# MAGI_sBoostPower.net
KiCad netlist of a schematic drawn in Altium Designer
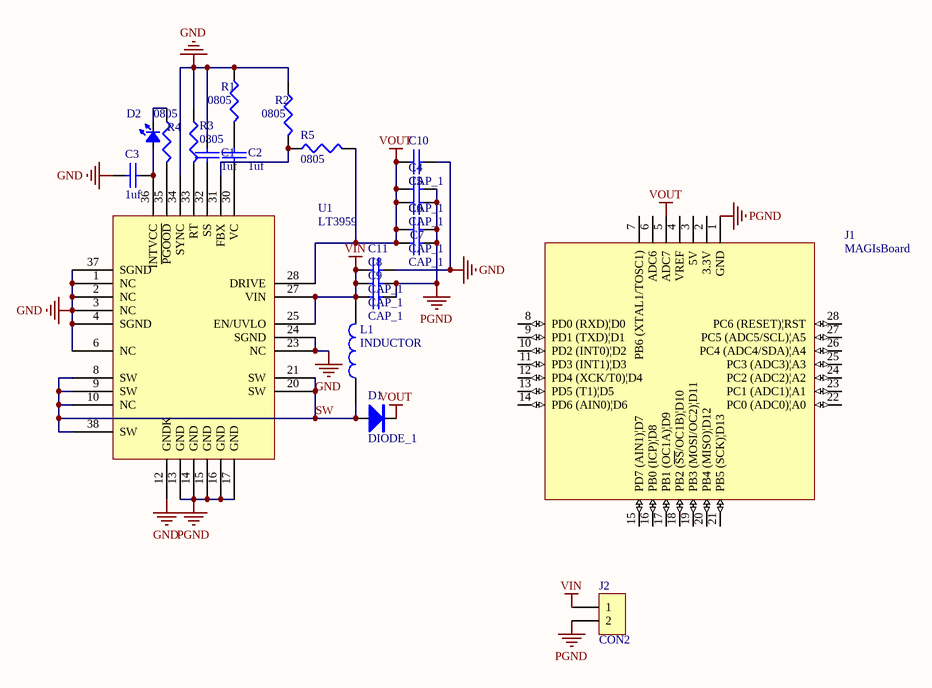
[diagram p0: MAGI'sBoostPower.SchDoc]

(export (version "E")
  (design (tool "Eeschema 10.0.6"))
  (components
    (comp (ref "C1")
      (value "1uf")
      (footprint "6-0805_N")
      (description "Capacitor")
      (libsource (lib "电容器") (part "CAP_1"))
    )
    (comp (ref "C2")
      (value "1uf")
      (footprint "6-0805_N")
      (description "Capacitor")
      (libsource (lib "电容器") (part "CAP_1"))
    )
    (comp (ref "C3")
      (value "1uf")
      (footprint "6-0805_N")
      (description "Capacitor")
      (libsource (lib "电容器") (part "CAP_1"))
    )
    (comp (ref "C4")
      (value "CAP_1")
      (footprint "C1206")
      (description "Capacitor")
      (libsource (lib "电容器") (part "CAP_1"))
    )
    (comp (ref "C5")
      (value "CAP_1")
      (footprint "C1206")
      (description "Capacitor")
      (libsource (lib "电容器") (part "CAP_1"))
    )
    (comp (ref "C6")
      (value "CAP_1")
      (footprint "C1206")
      (description "Capacitor")
      (libsource (lib "电容器") (part "CAP_1"))
    )
    (comp (ref "C7")
      (value "CAP_1")
      (footprint "C1206")
      (description "Capacitor")
      (libsource (lib "电容器") (part "CAP_1"))
    )
    (comp (ref "C8")
      (value "CAP_1")
      (footprint "C1206")
      (description "Capacitor")
      (libsource (lib "电容器") (part "CAP_1"))
    )
    (comp (ref "C9")
      (value "CAP_1")
      (footprint "C1206")
      (description "Capacitor")
      (libsource (lib "电容器") (part "CAP_1"))
    )
    (comp (ref "C10")
      (value "CAP_1")
      (footprint "6-0805_n")
      (description "Capacitor")
      (libsource (lib "电容器") (part "CAP_1"))
    )
    (comp (ref "C11")
      (value "CAP_1")
      (footprint "6-0805_n")
      (description "Capacitor")
      (libsource (lib "电容器") (part "CAP_1"))
    )
    (comp (ref "D1")
      (value "DIODE_1")
      (footprint "SMC")
      (description "Diode")
      (libsource (lib "二极管") (part "DIODE_1"))
    )
    (comp (ref "D2")
      (value "LED_0805")
      (footprint "6-0805_n")
      (description "LED")
      (libsource (lib "SCH_Active") (part "LED_0805"))
    )
    (comp (ref "J1")
      (value "MAGIsBoard")
      (footprint "MAGIsBoard")
      (libsource (lib "MAGIsBoard") (part "MAGIsBoard"))
    )
    (comp (ref "J2")
      (value "CON2")
      (footprint "T-Mini")
      (description "Connector")
      (libsource (lib "CON系列") (part "CON2"))
    )
    (comp (ref "L1") (value "INDUCTOR") (footprint "10*10") (libsource (lib "汇总") (part "INDUCTOR")))
    (comp (ref "R1") (value "0805") (footprint "6-0805_N") (libsource (lib "电阻器") (part "RES1_1")))
    (comp (ref "R2") (value "0805") (footprint "6-0805_N") (libsource (lib "电阻器") (part "RES1_1")))
    (comp (ref "R3") (value "0805") (footprint "6-0805_N") (libsource (lib "电阻器") (part "RES1_1")))
    (comp (ref "R4") (value "0805") (footprint "6-0805_N") (libsource (lib "电阻器") (part "RES1_1")))
    (comp (ref "R5") (value "0805") (footprint "6-0805_N") (libsource (lib "电阻器") (part "RES1_1")))
    (comp (ref "U1") (value "LT3959") (footprint "LT3959") (libsource (lib "PMIC") (part "LT3959")))
  )
  (nets
    (net (code "1") (name "/SW") (class "Default")
      (node (ref "D1") (pin "1") (pinfunction "A_1") (pintype "passive"))
      (node (ref "L1") (pin "1") (pinfunction "1_1") (pintype "passive"))
      (node (ref "U1") (pin "10") (pinfunction "NC_10") (pintype "passive"))
      (node (ref "U1") (pin "20") (pinfunction "SW_20") (pintype "passive"))
      (node (ref "U1") (pin "21") (pinfunction "SW_21") (pintype "passive"))
      (node (ref "U1") (pin "38") (pinfunction "SW_38") (pintype "passive"))
      (node (ref "U1") (pin "8") (pinfunction "SW_8") (pintype "passive"))
      (node (ref "U1") (pin "9") (pinfunction "SW_9") (pintype "passive"))
    )
    (net (code "2") (name "GND") (class "Default")
      (node (ref "C1") (pin "2") (pinfunction "2_2") (pintype "passive"))
      (node (ref "C10") (pin "2") (pinfunction "2_2") (pintype "passive"))
      (node (ref "C11") (pin "2") (pinfunction "2_2") (pintype "passive"))
      (node (ref "C3") (pin "2") (pinfunction "2_2") (pintype "passive"))
      (node (ref "R1") (pin "1") (pinfunction "1_1") (pintype "passive"))
      (node (ref "R2") (pin "1") (pinfunction "1_1") (pintype "passive"))
      (node (ref "R3") (pin "1") (pinfunction "1_1") (pintype "passive"))
      (node (ref "U1") (pin "1") (pinfunction "NC_1") (pintype "passive"))
      (node (ref "U1") (pin "12") (pinfunction "GNDK_12") (pintype "passive"))
      (node (ref "U1") (pin "2") (pinfunction "NC_2") (pintype "passive"))
      (node (ref "U1") (pin "23") (pinfunction "NC_23") (pintype "passive"))
      (node (ref "U1") (pin "24") (pinfunction "SGND_24") (pintype "passive"))
      (node (ref "U1") (pin "3") (pinfunction "NC_3") (pintype "passive"))
      (node (ref "U1") (pin "34") (pinfunction "SYNC_34") (pintype "passive"))
      (node (ref "U1") (pin "37") (pinfunction "SGND_37") (pintype "passive"))
      (node (ref "U1") (pin "4") (pinfunction "SGND_4") (pintype "passive"))
      (node (ref "U1") (pin "6") (pinfunction "NC_6") (pintype "passive"))
    )
    (net (code "3") (name "Net-(C2-Pad2)") (class "Default")
      (node (ref "C2") (pin "2") (pinfunction "2_2") (pintype "passive"))
      (node (ref "R1") (pin "2") (pinfunction "2_2") (pintype "passive"))
    )
    (net (code "4") (name "Net-(D2-A)") (class "Default")
      (node (ref "C3") (pin "1") (pinfunction "1_1") (pintype "passive"))
      (node (ref "D2") (pin "1") (pinfunction "A_1") (pintype "passive"))
      (node (ref "U1") (pin "36") (pinfunction "INTVCC_36") (pintype "passive"))
    )
    (net (code "5") (name "Net-(D2-K)") (class "Default")
      (node (ref "D2") (pin "2") (pinfunction "K_2") (pintype "passive"))
      (node (ref "R4") (pin "1") (pinfunction "1_1") (pintype "passive"))
    )
    (net (code "6") (name "Net-(U1-FBX)") (class "Default")
      (node (ref "R2") (pin "2") (pinfunction "2_2") (pintype "passive"))
      (node (ref "R5") (pin "1") (pinfunction "1_1") (pintype "passive"))
      (node (ref "U1") (pin "31") (pinfunction "FBX_31") (pintype "passive"))
    )
    (net (code "7") (name "Net-(U1-RT)") (class "Default")
      (node (ref "R3") (pin "2") (pinfunction "2_2") (pintype "passive"))
      (node (ref "U1") (pin "33") (pinfunction "RT_33") (pintype "passive"))
    )
    (net (code "8") (name "Net-(U1-SS)") (class "Default")
      (node (ref "C1") (pin "1") (pinfunction "1_1") (pintype "passive"))
      (node (ref "U1") (pin "32") (pinfunction "SS_32") (pintype "passive"))
    )
    (net (code "9") (name "Net-(U1-VC)") (class "Default")
      (node (ref "C2") (pin "1") (pinfunction "1_1") (pintype "passive"))
      (node (ref "U1") (pin "30") (pinfunction "VC_30") (pintype "passive"))
    )
    (net (code "10") (name "Net-(U1-~{PGOOD})") (class "Default")
      (node (ref "R4") (pin "2") (pinfunction "2_2") (pintype "passive"))
      (node (ref "U1") (pin "35") (pinfunction "~{PGOOD}_35") (pintype "passive"))
    )
    (net (code "11") (name "PGND") (class "Default")
      (node (ref "C4") (pin "2") (pinfunction "2_2") (pintype "passive"))
      (node (ref "C5") (pin "2") (pinfunction "2_2") (pintype "passive"))
      (node (ref "C6") (pin "2") (pinfunction "2_2") (pintype "passive"))
      (node (ref "C7") (pin "2") (pinfunction "2_2") (pintype "passive"))
      (node (ref "C8") (pin "2") (pinfunction "2_2") (pintype "passive"))
      (node (ref "C9") (pin "2") (pinfunction "2_2") (pintype "passive"))
      (node (ref "J1") (pin "1") (pinfunction "GND_1") (pintype "power_in"))
      (node (ref "J2") (pin "2") (pinfunction "2_2") (pintype "passive"))
      (node (ref "U1") (pin "13") (pinfunction "GND_13") (pintype "passive"))
      (node (ref "U1") (pin "14") (pinfunction "GND_14") (pintype "passive"))
      (node (ref "U1") (pin "15") (pinfunction "GND_15") (pintype "passive"))
      (node (ref "U1") (pin "16") (pinfunction "GND_16") (pintype "passive"))
      (node (ref "U1") (pin "17") (pinfunction "GND_17") (pintype "passive"))
    )
    (net (code "12") (name "VIN") (class "Default")
      (node (ref "C11") (pin "1") (pinfunction "1_1") (pintype "passive"))
      (node (ref "C8") (pin "1") (pinfunction "1_1") (pintype "passive"))
      (node (ref "C9") (pin "1") (pinfunction "1_1") (pintype "passive"))
      (node (ref "J2") (pin "1") (pinfunction "1_1") (pintype "passive"))
      (node (ref "L1") (pin "2") (pinfunction "2_2") (pintype "passive"))
      (node (ref "U1") (pin "25") (pinfunction "EN/UVLO_25") (pintype "passive"))
      (node (ref "U1") (pin "27") (pinfunction "VIN_27") (pintype "passive"))
    )
    (net (code "13") (name "VOUT") (class "Default")
      (node (ref "C10") (pin "1") (pinfunction "1_1") (pintype "passive"))
      (node (ref "C4") (pin "1") (pinfunction "1_1") (pintype "passive"))
      (node (ref "C5") (pin "1") (pinfunction "1_1") (pintype "passive"))
      (node (ref "C6") (pin "1") (pinfunction "1_1") (pintype "passive"))
      (node (ref "C7") (pin "1") (pinfunction "1_1") (pintype "passive"))
      (node (ref "D1") (pin "2") (pinfunction "K_2") (pintype "passive"))
      (node (ref "J1") (pin "5") (pinfunction "ADC7_5") (pintype "passive"))
      (node (ref "R5") (pin "2") (pinfunction "2_2") (pintype "passive"))
      (node (ref "U1") (pin "28") (pinfunction "DRIVE_28") (pintype "passive"))
    )
    (net (code "14") (name "unconnected-(J1-3.3V-Pad2)") (class "Default")
      (node (ref "J1") (pin "2") (pinfunction "3.3V_2") (pintype "power_in"))
    )
    (net (code "15") (name "unconnected-(J1-5V-Pad3)") (class "Default")
      (node (ref "J1") (pin "3") (pinfunction "5V_3") (pintype "power_in"))
    )
    (net (code "16") (name "unconnected-(J1-ADC6-Pad6)") (class "Default")
      (node (ref "J1") (pin "6") (pinfunction "ADC6_6") (pintype "passive"))
    )
    (net (code "17") (name "unconnected-(J1-PB0_(ICP)¦D8-Pad16)") (class "Default")
      (node (ref "J1") (pin "16") (pinfunction "PB0_(ICP)¦D8_16") (pintype "bidirectional"))
    )
    (net (code "18") (name "unconnected-(J1-PB1_(OC1A)¦D9-Pad17)") (class "Default")
      (node (ref "J1") (pin "17") (pinfunction "PB1_(OC1A)¦D9_17") (pintype "bidirectional"))
    )
    (net (code "19") (name "unconnected-(J1-PB2_(~{SS}{slash}OC1B)¦D10-Pad18)") (class "Default")
      (node (ref "J1") (pin "18") (pinfunction "PB2_(~{SS}/OC1B)¦D10_18") (pintype "bidirectional"))
    )
    (net (code "20") (name "unconnected-(J1-PB3_(MOSI{slash}OC2)¦D11-Pad19)") (class "Default")
      (node (ref "J1") (pin "19") (pinfunction "PB3_(MOSI/OC2)¦D11_19") (pintype "bidirectional"))
    )
    (net (code "21") (name "unconnected-(J1-PB4_(MISO)¦D12-Pad20)") (class "Default")
      (node (ref "J1") (pin "20") (pinfunction "PB4_(MISO)¦D12_20") (pintype "bidirectional"))
    )
    (net (code "22") (name "unconnected-(J1-PB5_(SCK)¦D13-Pad21)") (class "Default")
      (node (ref "J1") (pin "21") (pinfunction "PB5_(SCK)¦D13_21") (pintype "bidirectional"))
    )
    (net (code "23") (name "unconnected-(J1-PB6_(XTAL1{slash}TOSC1)-Pad7)") (class "Default")
      (node (ref "J1") (pin "7") (pinfunction "PB6_(XTAL1/TOSC1)_7") (pintype "passive"))
    )
    (net (code "24") (name "unconnected-(J1-PC0_(ADC0)¦A0-Pad22)") (class "Default")
      (node (ref "J1") (pin "22") (pinfunction "PC0_(ADC0)¦A0_22") (pintype "bidirectional"))
    )
    (net (code "25") (name "unconnected-(J1-PC1_(ADC1)¦A1-Pad23)") (class "Default")
      (node (ref "J1") (pin "23") (pinfunction "PC1_(ADC1)¦A1_23") (pintype "bidirectional"))
    )
    (net (code "26") (name "unconnected-(J1-PC2_(ADC2)¦A2-Pad24)") (class "Default")
      (node (ref "J1") (pin "24") (pinfunction "PC2_(ADC2)¦A2_24") (pintype "bidirectional"))
    )
    (net (code "27") (name "unconnected-(J1-PC3_(ADC3)¦A3-Pad25)") (class "Default")
      (node (ref "J1") (pin "25") (pinfunction "PC3_(ADC3)¦A3_25") (pintype "bidirectional"))
    )
    (net (code "28") (name "unconnected-(J1-PC4_(ADC4{slash}SDA)¦A4-Pad26)") (class "Default")
      (node (ref "J1") (pin "26") (pinfunction "PC4_(ADC4/SDA)¦A4_26") (pintype "bidirectional"))
    )
    (net (code "29") (name "unconnected-(J1-PC5_(ADC5{slash}SCL)¦A5-Pad27)") (class "Default")
      (node (ref "J1") (pin "27") (pinfunction "PC5_(ADC5/SCL)¦A5_27") (pintype "bidirectional"))
    )
    (net (code "30") (name "unconnected-(J1-PC6_(RESET)¦RST-Pad28)") (class "Default")
      (node (ref "J1") (pin "28") (pinfunction "PC6_(RESET)¦RST_28") (pintype "bidirectional"))
    )
    (net (code "31") (name "unconnected-(J1-PD0_(RXD)¦D0-Pad8)") (class "Default")
      (node (ref "J1") (pin "8") (pinfunction "PD0_(RXD)¦D0_8") (pintype "bidirectional"))
    )
    (net (code "32") (name "unconnected-(J1-PD1_(TXD)¦D1-Pad9)") (class "Default")
      (node (ref "J1") (pin "9") (pinfunction "PD1_(TXD)¦D1_9") (pintype "bidirectional"))
    )
    (net (code "33") (name "unconnected-(J1-PD2_(INT0)¦D2-Pad10)") (class "Default")
      (node (ref "J1") (pin "10") (pinfunction "PD2_(INT0)¦D2_10") (pintype "bidirectional"))
    )
    (net (code "34") (name "unconnected-(J1-PD3_(INT1)¦D3-Pad11)") (class "Default")
      (node (ref "J1") (pin "11") (pinfunction "PD3_(INT1)¦D3_11") (pintype "bidirectional"))
    )
    (net (code "35") (name "unconnected-(J1-PD4_(XCK{slash}T0)¦D4-Pad12)") (class "Default")
      (node (ref "J1") (pin "12") (pinfunction "PD4_(XCK/T0)¦D4_12") (pintype "bidirectional"))
    )
    (net (code "36") (name "unconnected-(J1-PD5_(T1)¦D5-Pad13)") (class "Default")
      (node (ref "J1") (pin "13") (pinfunction "PD5_(T1)¦D5_13") (pintype "bidirectional"))
    )
    (net (code "37") (name "unconnected-(J1-PD6_(AIN0)¦D6-Pad14)") (class "Default")
      (node (ref "J1") (pin "14") (pinfunction "PD6_(AIN0)¦D6_14") (pintype "bidirectional"))
    )
    (net (code "38") (name "unconnected-(J1-PD7_(AIN1)¦D7-Pad15)") (class "Default")
      (node (ref "J1") (pin "15") (pinfunction "PD7_(AIN1)¦D7_15") (pintype "bidirectional"))
    )
    (net (code "39") (name "unconnected-(J1-VREF-Pad4)") (class "Default")
      (node (ref "J1") (pin "4") (pinfunction "VREF_4") (pintype "passive"))
    )
  )
)
